# 4-UniverseOut.net
KiCad netlist of a schematic drawn in EAGLE
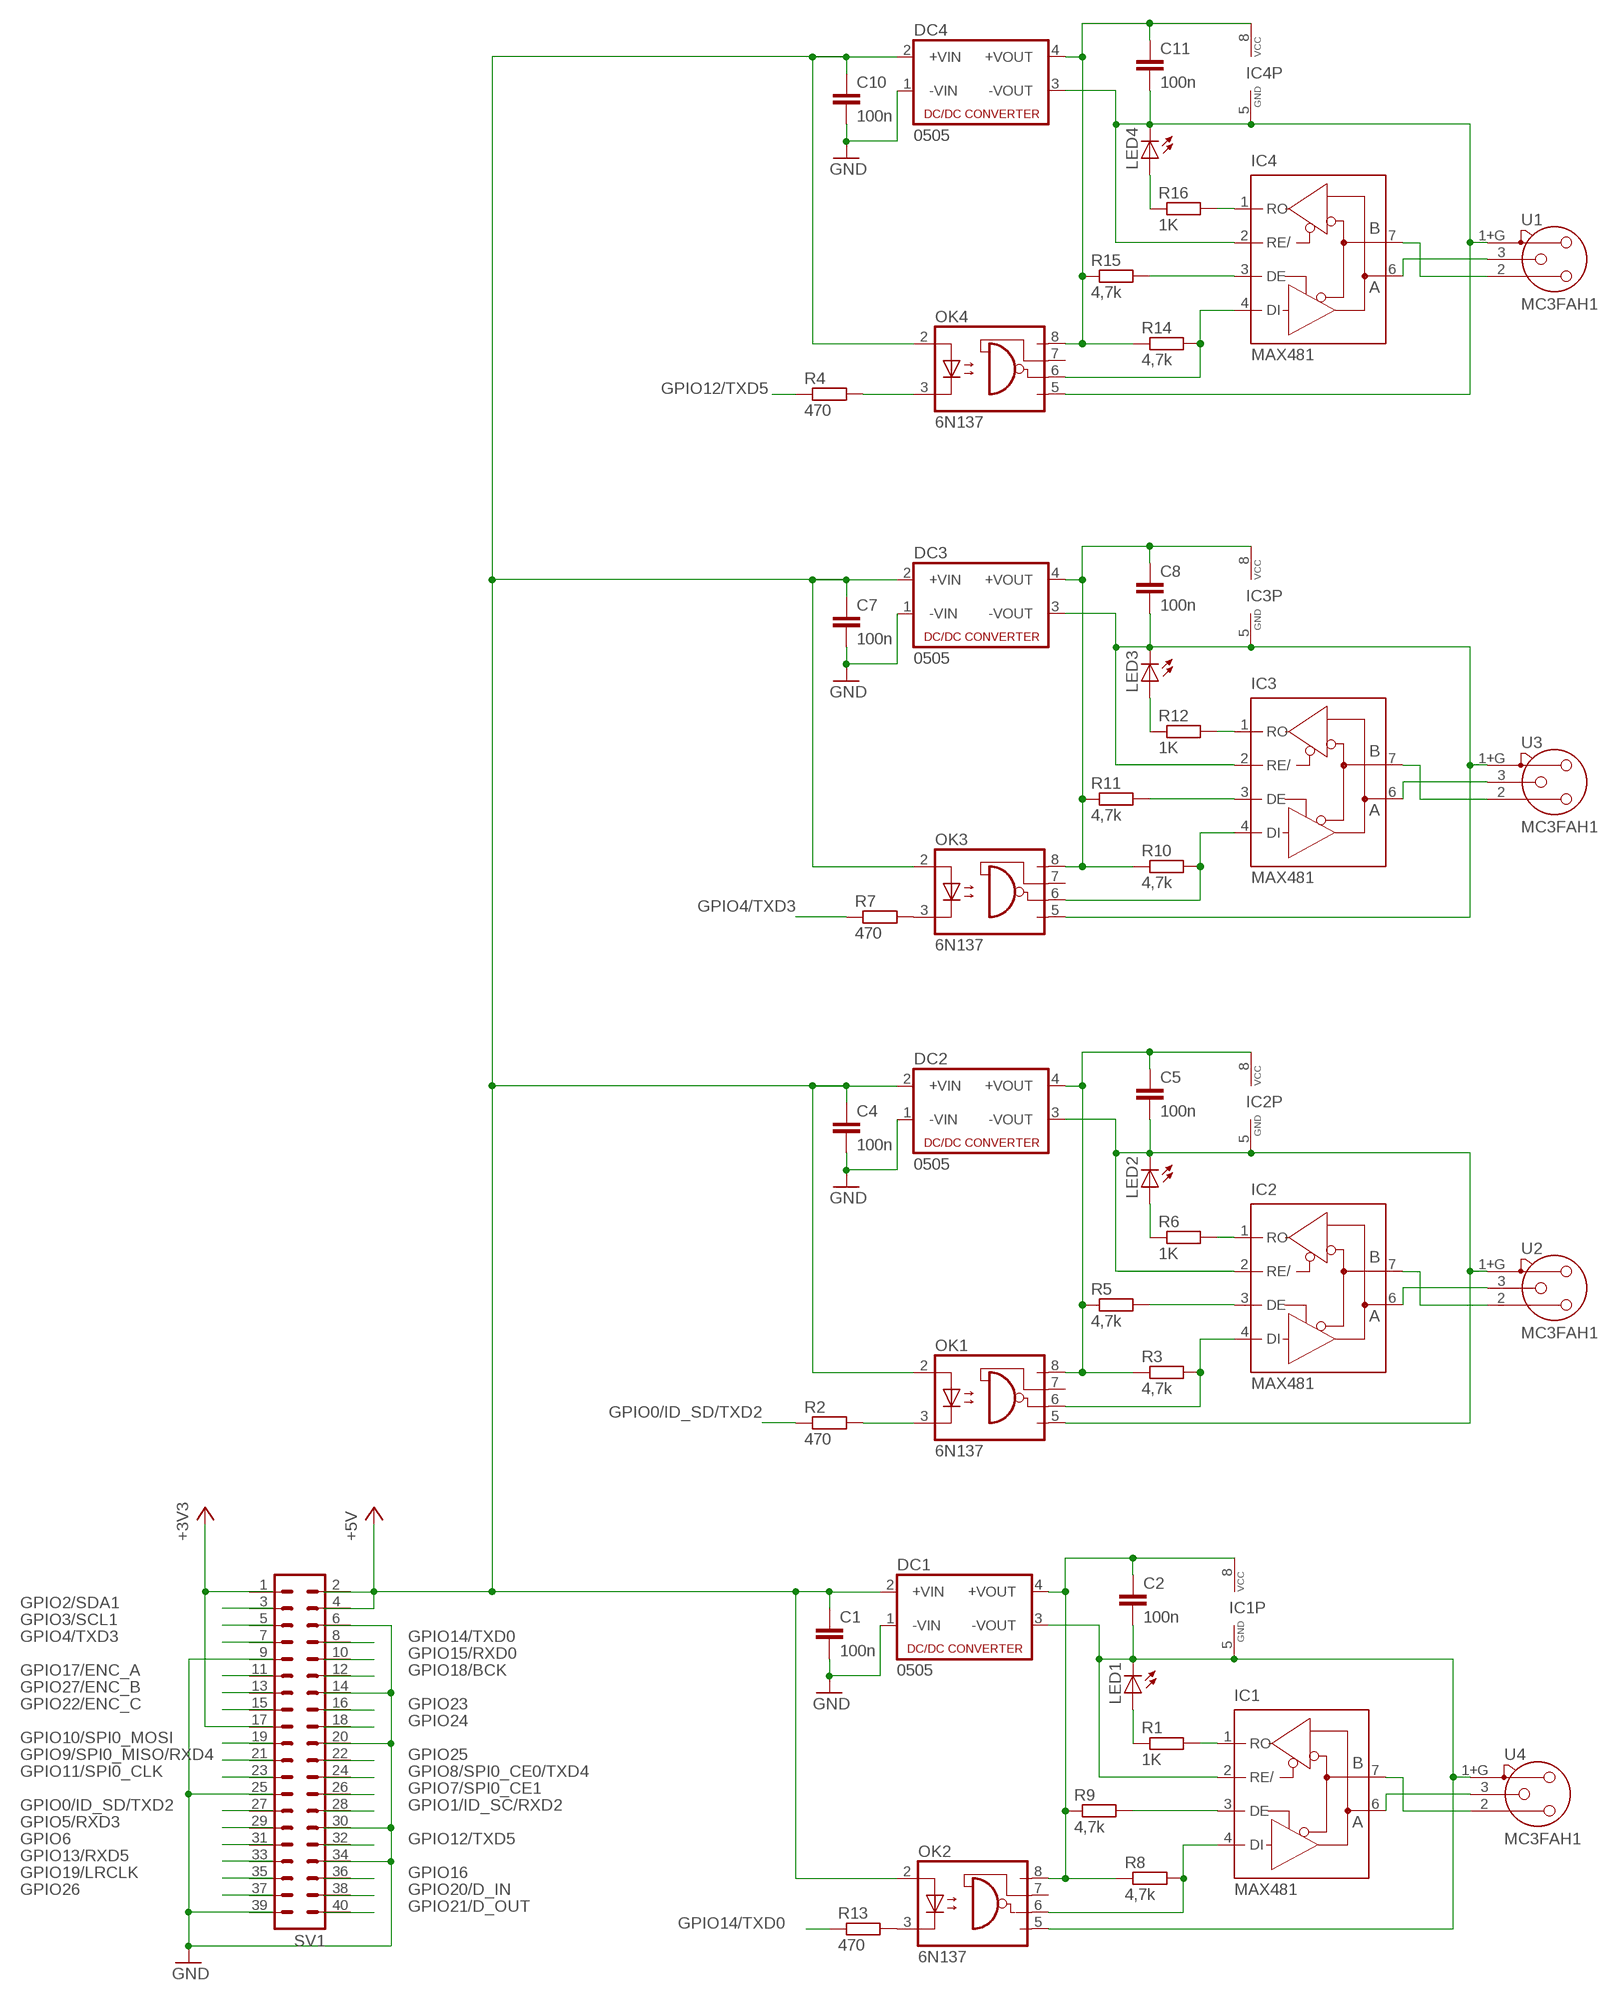
[diagram p0: schematic, sheet 1]

(export (version "E")
  (design (tool "Eeschema 10.0.6"))
  (components
    (comp (ref "C1")
      (value "100n")
      (footprint "eagle-import:C5B3")
      (libsource (lib "eagle-import") (part "C5/3"))
    )
    (comp (ref "C2")
      (value "100n")
      (footprint "eagle-import:C7.5B3")
      (libsource (lib "eagle-import") (part "C7.5/3"))
    )
    (comp (ref "C4")
      (value "100n")
      (footprint "eagle-import:C5B3")
      (libsource (lib "eagle-import") (part "C5/3"))
    )
    (comp (ref "C5")
      (value "100n")
      (footprint "eagle-import:C7.5B3")
      (libsource (lib "eagle-import") (part "C7.5/3"))
    )
    (comp (ref "C7")
      (value "100n")
      (footprint "eagle-import:C5B3")
      (libsource (lib "eagle-import") (part "C5/3"))
    )
    (comp (ref "C8")
      (value "100n")
      (footprint "eagle-import:C7.5B3")
      (libsource (lib "eagle-import") (part "C7.5/3"))
    )
    (comp (ref "C10")
      (value "100n")
      (footprint "eagle-import:C5B3")
      (libsource (lib "eagle-import") (part "C5/3"))
    )
    (comp (ref "C11")
      (value "100n")
      (footprint "eagle-import:C7.5B3")
      (libsource (lib "eagle-import") (part "C7.5/3"))
    )
    (comp (ref "DC1")
      (value "0505")
      (footprint "eagle-import:NME")
      (fields (field (name "MF") "C & D TECHNOLOGIES, INC") (field (name "MPN") "NME1205D"))
      (libsource (lib "eagle-import") (part "NME"))
    )
    (comp (ref "DC2")
      (value "0505")
      (footprint "eagle-import:NME")
      (fields (field (name "MF") "C & D TECHNOLOGIES, INC") (field (name "MPN") "NME1205D"))
      (libsource (lib "eagle-import") (part "NME"))
    )
    (comp (ref "DC3")
      (value "0505")
      (footprint "eagle-import:NME")
      (fields (field (name "MF") "C & D TECHNOLOGIES, INC") (field (name "MPN") "NME1205D"))
      (libsource (lib "eagle-import") (part "NME"))
    )
    (comp (ref "DC4")
      (value "0505")
      (footprint "eagle-import:NME")
      (fields (field (name "MF") "C & D TECHNOLOGIES, INC") (field (name "MPN") "NME1205D"))
      (libsource (lib "eagle-import") (part "NME"))
    )
    (comp (ref "IC1")
      (value "MAX481")
      (footprint "eagle-import:DIL08")
      (fields (field (name "MPN") "MAX481CPA+"))
      (libsource (lib "eagle-import") (part "MAX481CPA"))
    )
    (comp (ref "IC2")
      (value "MAX481")
      (footprint "eagle-import:DIL08")
      (fields (field (name "MPN") "MAX481CPA+"))
      (libsource (lib "eagle-import") (part "MAX481CPA"))
    )
    (comp (ref "IC3")
      (value "MAX481")
      (footprint "eagle-import:DIL08")
      (fields (field (name "MPN") "MAX481CPA+"))
      (libsource (lib "eagle-import") (part "MAX481CPA"))
    )
    (comp (ref "IC4")
      (value "MAX481")
      (footprint "eagle-import:DIL08")
      (fields (field (name "MPN") "MAX481CPA+"))
      (libsource (lib "eagle-import") (part "MAX481CPA"))
    )
    (comp (ref "LED1")
      (value "LED3MM")
      (footprint "eagle-import:LED3MM")
      (libsource (lib "eagle-import") (part "LED3MM"))
    )
    (comp (ref "LED2")
      (value "LED3MM")
      (footprint "eagle-import:LED3MM")
      (libsource (lib "eagle-import") (part "LED3MM"))
    )
    (comp (ref "LED3")
      (value "LED3MM")
      (footprint "eagle-import:LED3MM")
      (libsource (lib "eagle-import") (part "LED3MM"))
    )
    (comp (ref "LED4")
      (value "LED3MM")
      (footprint "eagle-import:LED3MM")
      (libsource (lib "eagle-import") (part "LED3MM"))
    )
    (comp (ref "OK1")
      (value "6N137")
      (footprint "eagle-import:DIL08")
      (libsource (lib "eagle-import") (part "6N137"))
    )
    (comp (ref "OK2")
      (value "6N137")
      (footprint "eagle-import:DIL08")
      (libsource (lib "eagle-import") (part "6N137"))
    )
    (comp (ref "OK3")
      (value "6N137")
      (footprint "eagle-import:DIL08")
      (libsource (lib "eagle-import") (part "6N137"))
    )
    (comp (ref "OK4")
      (value "6N137")
      (footprint "eagle-import:DIL08")
      (libsource (lib "eagle-import") (part "6N137"))
    )
    (comp (ref "R1")
      (value "1K")
      (footprint "eagle-import:0204_7")
      (libsource (lib "eagle-import") (part "R-EU_0204/7"))
    )
    (comp (ref "R2")
      (value "470")
      (footprint "eagle-import:0207_12")
      (libsource (lib "eagle-import") (part "R-EU_0207/12"))
    )
    (comp (ref "R3")
      (value "4,7k")
      (footprint "eagle-import:0204_7")
      (libsource (lib "eagle-import") (part "R-EU_0204/7"))
    )
    (comp (ref "R4")
      (value "470")
      (footprint "eagle-import:0204_7")
      (libsource (lib "eagle-import") (part "R-EU_0204/7"))
    )
    (comp (ref "R5")
      (value "4,7k")
      (footprint "eagle-import:0204_7")
      (libsource (lib "eagle-import") (part "R-EU_0204/7"))
    )
    (comp (ref "R6")
      (value "1K")
      (footprint "eagle-import:0204_7")
      (libsource (lib "eagle-import") (part "R-EU_0204/7"))
    )
    (comp (ref "R7")
      (value "470")
      (footprint "eagle-import:0204_7")
      (libsource (lib "eagle-import") (part "R-EU_0204/7"))
    )
    (comp (ref "R8")
      (value "4,7k")
      (footprint "eagle-import:0204_7")
      (libsource (lib "eagle-import") (part "R-EU_0204/7"))
    )
    (comp (ref "R9")
      (value "4,7k")
      (footprint "eagle-import:0204_7")
      (libsource (lib "eagle-import") (part "R-EU_0204/7"))
    )
    (comp (ref "R10")
      (value "4,7k")
      (footprint "eagle-import:0204_7")
      (libsource (lib "eagle-import") (part "R-EU_0204/7"))
    )
    (comp (ref "R11")
      (value "4,7k")
      (footprint "eagle-import:0204_7")
      (libsource (lib "eagle-import") (part "R-EU_0204/7"))
    )
    (comp (ref "R12")
      (value "1K")
      (footprint "eagle-import:0204_7")
      (libsource (lib "eagle-import") (part "R-EU_0204/7"))
    )
    (comp (ref "R13")
      (value "470")
      (footprint "eagle-import:0204_7")
      (libsource (lib "eagle-import") (part "R-EU_0204/7"))
    )
    (comp (ref "R14")
      (value "4,7k")
      (footprint "eagle-import:0204_7")
      (libsource (lib "eagle-import") (part "R-EU_0204/7"))
    )
    (comp (ref "R15")
      (value "4,7k")
      (footprint "eagle-import:0204_7")
      (libsource (lib "eagle-import") (part "R-EU_0204/7"))
    )
    (comp (ref "R16")
      (value "1K")
      (footprint "eagle-import:0204_7")
      (libsource (lib "eagle-import") (part "R-EU_0204/7"))
    )
    (comp (ref "SV1")
      (value "ML40")
      (footprint "eagle-import:ML40")
      (libsource (lib "eagle-import") (part "ML40"))
    )
    (comp (ref "U1")
      (value "MC3FAH1")
      (footprint "eagle-import:NC3FAH1")
      (libsource (lib "eagle-import") (part "MC3?FAH1"))
    )
    (comp (ref "U2")
      (value "MC3FAH1")
      (footprint "eagle-import:NC3FAH1")
      (libsource (lib "eagle-import") (part "MC3?FAH1"))
    )
    (comp (ref "U3")
      (value "MC3FAH1")
      (footprint "eagle-import:NC3FAH1")
      (libsource (lib "eagle-import") (part "MC3?FAH1"))
    )
    (comp (ref "U4")
      (value "MC3FAH1")
      (footprint "eagle-import:NC3FAH1")
      (libsource (lib "eagle-import") (part "MC3?FAH1"))
    )
  )
  (nets
    (net (code "1") (name "+3V3") (class "Default")
      (node (ref "SV1") (pin "1") (pinfunction "1_1") (pintype "passive"))
      (node (ref "SV1") (pin "17") (pinfunction "17_17") (pintype "passive"))
    )
    (net (code "2") (name "+5V") (class "Default")
      (node (ref "C1") (pin "1") (pinfunction "1_1") (pintype "passive"))
      (node (ref "C10") (pin "1") (pinfunction "1_1") (pintype "passive"))
      (node (ref "C4") (pin "1") (pinfunction "1_1") (pintype "passive"))
      (node (ref "C7") (pin "1") (pinfunction "1_1") (pintype "passive"))
      (node (ref "DC1") (pin "2") (pinfunction "+VIN_2") (pintype "passive"))
      (node (ref "DC2") (pin "2") (pinfunction "+VIN_2") (pintype "passive"))
      (node (ref "DC3") (pin "2") (pinfunction "+VIN_2") (pintype "passive"))
      (node (ref "DC4") (pin "2") (pinfunction "+VIN_2") (pintype "passive"))
      (node (ref "OK1") (pin "2") (pinfunction "A_2") (pintype "passive"))
      (node (ref "OK2") (pin "2") (pinfunction "A_2") (pintype "passive"))
      (node (ref "OK3") (pin "2") (pinfunction "A_2") (pintype "passive"))
      (node (ref "OK4") (pin "2") (pinfunction "A_2") (pintype "passive"))
      (node (ref "SV1") (pin "2") (pinfunction "2_2") (pintype "passive"))
      (node (ref "SV1") (pin "4") (pinfunction "4_4") (pintype "passive"))
    )
    (net (code "3") (name "/GPIO0{slash}ID_SD{slash}TXD2") (class "Default")
      (node (ref "R2") (pin "1") (pinfunction "1_1") (pintype "passive"))
      (node (ref "SV1") (pin "27") (pinfunction "27_27") (pintype "passive"))
    )
    (net (code "4") (name "/GPIO1{slash}ID_SC{slash}RXD2") (class "Default")
      (node (ref "SV1") (pin "28") (pinfunction "28_28") (pintype "passive"))
    )
    (net (code "5") (name "/GPIO2{slash}SDA1") (class "Default")
      (node (ref "SV1") (pin "3") (pinfunction "3_3") (pintype "passive"))
    )
    (net (code "6") (name "/GPIO3{slash}SCL1") (class "Default")
      (node (ref "SV1") (pin "5") (pinfunction "5_5") (pintype "passive"))
    )
    (net (code "7") (name "/GPIO4{slash}TXD3") (class "Default")
      (node (ref "R7") (pin "1") (pinfunction "1_1") (pintype "passive"))
      (node (ref "SV1") (pin "7") (pinfunction "7_7") (pintype "passive"))
    )
    (net (code "8") (name "/GPIO5{slash}RXD3") (class "Default")
      (node (ref "SV1") (pin "29") (pinfunction "29_29") (pintype "passive"))
    )
    (net (code "9") (name "/GPIO6") (class "Default")
      (node (ref "SV1") (pin "31") (pinfunction "31_31") (pintype "passive"))
    )
    (net (code "10") (name "/GPIO7{slash}SPI0_CE1") (class "Default")
      (node (ref "SV1") (pin "26") (pinfunction "26_26") (pintype "passive"))
    )
    (net (code "11") (name "/GPIO8{slash}SPI0_CE0{slash}TXD4") (class "Default")
      (node (ref "SV1") (pin "24") (pinfunction "24_24") (pintype "passive"))
    )
    (net (code "12") (name "/GPIO9{slash}SPI0_MISO{slash}RXD4") (class "Default")
      (node (ref "SV1") (pin "21") (pinfunction "21_21") (pintype "passive"))
    )
    (net (code "13") (name "/GPIO10{slash}SPI0_MOSI") (class "Default")
      (node (ref "SV1") (pin "19") (pinfunction "19_19") (pintype "passive"))
    )
    (net (code "14") (name "/GPIO11{slash}SPI0_CLK") (class "Default")
      (node (ref "SV1") (pin "23") (pinfunction "23_23") (pintype "passive"))
    )
    (net (code "15") (name "/GPIO12{slash}TXD5") (class "Default")
      (node (ref "R4") (pin "1") (pinfunction "1_1") (pintype "passive"))
      (node (ref "SV1") (pin "32") (pinfunction "32_32") (pintype "passive"))
    )
    (net (code "16") (name "/GPIO13{slash}RXD5") (class "Default")
      (node (ref "SV1") (pin "33") (pinfunction "33_33") (pintype "passive"))
    )
    (net (code "17") (name "/GPIO14{slash}TXD0") (class "Default")
      (node (ref "R13") (pin "1") (pinfunction "1_1") (pintype "passive"))
      (node (ref "SV1") (pin "8") (pinfunction "8_8") (pintype "passive"))
    )
    (net (code "18") (name "/GPIO15{slash}RXD0") (class "Default")
      (node (ref "SV1") (pin "10") (pinfunction "10_10") (pintype "passive"))
    )
    (net (code "19") (name "/GPIO16") (class "Default")
      (node (ref "SV1") (pin "36") (pinfunction "36_36") (pintype "passive"))
    )
    (net (code "20") (name "/GPIO17{slash}ENC_A") (class "Default")
      (node (ref "SV1") (pin "11") (pinfunction "11_11") (pintype "passive"))
    )
    (net (code "21") (name "/GPIO18{slash}BCK") (class "Default")
      (node (ref "SV1") (pin "12") (pinfunction "12_12") (pintype "passive"))
    )
    (net (code "22") (name "/GPIO19{slash}LRCLK") (class "Default")
      (node (ref "SV1") (pin "35") (pinfunction "35_35") (pintype "passive"))
    )
    (net (code "23") (name "/GPIO20{slash}D_IN") (class "Default")
      (node (ref "SV1") (pin "38") (pinfunction "38_38") (pintype "passive"))
    )
    (net (code "24") (name "/GPIO21{slash}D_OUT") (class "Default")
      (node (ref "SV1") (pin "40") (pinfunction "40_40") (pintype "passive"))
    )
    (net (code "25") (name "/GPIO22{slash}ENC_C") (class "Default")
      (node (ref "SV1") (pin "15") (pinfunction "15_15") (pintype "passive"))
    )
    (net (code "26") (name "/GPIO23") (class "Default")
      (node (ref "SV1") (pin "16") (pinfunction "16_16") (pintype "passive"))
    )
    (net (code "27") (name "/GPIO24") (class "Default")
      (node (ref "SV1") (pin "18") (pinfunction "18_18") (pintype "passive"))
    )
    (net (code "28") (name "/GPIO25") (class "Default")
      (node (ref "SV1") (pin "22") (pinfunction "22_22") (pintype "passive"))
    )
    (net (code "29") (name "/GPIO26") (class "Default")
      (node (ref "SV1") (pin "37") (pinfunction "37_37") (pintype "passive"))
    )
    (net (code "30") (name "/GPIO27{slash}ENC_B") (class "Default")
      (node (ref "SV1") (pin "13") (pinfunction "13_13") (pintype "passive"))
    )
    (net (code "31") (name "GND") (class "Default")
      (node (ref "C1") (pin "2") (pinfunction "2_2") (pintype "passive"))
      (node (ref "C10") (pin "2") (pinfunction "2_2") (pintype "passive"))
      (node (ref "C4") (pin "2") (pinfunction "2_2") (pintype "passive"))
      (node (ref "C7") (pin "2") (pinfunction "2_2") (pintype "passive"))
      (node (ref "DC1") (pin "1") (pinfunction "-VIN_1") (pintype "passive"))
      (node (ref "DC2") (pin "1") (pinfunction "-VIN_1") (pintype "passive"))
      (node (ref "DC3") (pin "1") (pinfunction "-VIN_1") (pintype "passive"))
      (node (ref "DC4") (pin "1") (pinfunction "-VIN_1") (pintype "passive"))
      (node (ref "SV1") (pin "14") (pinfunction "14_14") (pintype "passive"))
      (node (ref "SV1") (pin "20") (pinfunction "20_20") (pintype "passive"))
      (node (ref "SV1") (pin "25") (pinfunction "25_25") (pintype "passive"))
      (node (ref "SV1") (pin "30") (pinfunction "30_30") (pintype "passive"))
      (node (ref "SV1") (pin "34") (pinfunction "34_34") (pintype "passive"))
      (node (ref "SV1") (pin "39") (pinfunction "39_39") (pintype "passive"))
      (node (ref "SV1") (pin "6") (pinfunction "6_6") (pintype "passive"))
      (node (ref "SV1") (pin "9") (pinfunction "9_9") (pintype "passive"))
    )
    (net (code "32") (name "Net-(DC1-+VOUT)") (class "Default")
      (node (ref "C2") (pin "1") (pinfunction "1_1") (pintype "passive"))
      (node (ref "DC1") (pin "4") (pinfunction "+VOUT_4") (pintype "passive"))
      (node (ref "IC1") (pin "8") (pinfunction "VCC_8") (pintype "power_in"))
      (node (ref "OK2") (pin "8") (pinfunction "VCC_8") (pintype "passive"))
      (node (ref "R8") (pin "1") (pinfunction "1_1") (pintype "passive"))
      (node (ref "R9") (pin "1") (pinfunction "1_1") (pintype "passive"))
    )
    (net (code "33") (name "Net-(DC1--VOUT)") (class "Default")
      (node (ref "C2") (pin "2") (pinfunction "2_2") (pintype "passive"))
      (node (ref "DC1") (pin "3") (pinfunction "-VOUT_3") (pintype "passive"))
      (node (ref "IC1") (pin "2") (pinfunction "RE/_2") (pintype "input"))
      (node (ref "IC1") (pin "5") (pinfunction "GND_5") (pintype "power_in"))
      (node (ref "LED1") (pin "K") (pinfunction "C_K") (pintype "passive"))
      (node (ref "OK2") (pin "5") (pinfunction "GND_5") (pintype "passive"))
      (node (ref "U4") (pin "1+G") (pinfunction "1_1+G") (pintype "passive"))
    )
    (net (code "34") (name "Net-(DC2-+VOUT)") (class "Default")
      (node (ref "C5") (pin "1") (pinfunction "1_1") (pintype "passive"))
      (node (ref "DC2") (pin "4") (pinfunction "+VOUT_4") (pintype "passive"))
      (node (ref "IC2") (pin "8") (pinfunction "VCC_8") (pintype "power_in"))
      (node (ref "OK1") (pin "8") (pinfunction "VCC_8") (pintype "passive"))
      (node (ref "R3") (pin "1") (pinfunction "1_1") (pintype "passive"))
      (node (ref "R5") (pin "1") (pinfunction "1_1") (pintype "passive"))
    )
    (net (code "35") (name "Net-(DC2--VOUT)") (class "Default")
      (node (ref "C5") (pin "2") (pinfunction "2_2") (pintype "passive"))
      (node (ref "DC2") (pin "3") (pinfunction "-VOUT_3") (pintype "passive"))
      (node (ref "IC2") (pin "2") (pinfunction "RE/_2") (pintype "input"))
      (node (ref "IC2") (pin "5") (pinfunction "GND_5") (pintype "power_in"))
      (node (ref "LED2") (pin "K") (pinfunction "C_K") (pintype "passive"))
      (node (ref "OK1") (pin "5") (pinfunction "GND_5") (pintype "passive"))
      (node (ref "U2") (pin "1+G") (pinfunction "1_1+G") (pintype "passive"))
    )
    (net (code "36") (name "Net-(DC3-+VOUT)") (class "Default")
      (node (ref "C8") (pin "1") (pinfunction "1_1") (pintype "passive"))
      (node (ref "DC3") (pin "4") (pinfunction "+VOUT_4") (pintype "passive"))
      (node (ref "IC3") (pin "8") (pinfunction "VCC_8") (pintype "power_in"))
      (node (ref "OK3") (pin "8") (pinfunction "VCC_8") (pintype "passive"))
      (node (ref "R10") (pin "1") (pinfunction "1_1") (pintype "passive"))
      (node (ref "R11") (pin "1") (pinfunction "1_1") (pintype "passive"))
    )
    (net (code "37") (name "Net-(DC3--VOUT)") (class "Default")
      (node (ref "C8") (pin "2") (pinfunction "2_2") (pintype "passive"))
      (node (ref "DC3") (pin "3") (pinfunction "-VOUT_3") (pintype "passive"))
      (node (ref "IC3") (pin "2") (pinfunction "RE/_2") (pintype "input"))
      (node (ref "IC3") (pin "5") (pinfunction "GND_5") (pintype "power_in"))
      (node (ref "LED3") (pin "K") (pinfunction "C_K") (pintype "passive"))
      (node (ref "OK3") (pin "5") (pinfunction "GND_5") (pintype "passive"))
      (node (ref "U3") (pin "1+G") (pinfunction "1_1+G") (pintype "passive"))
    )
    (net (code "38") (name "Net-(DC4-+VOUT)") (class "Default")
      (node (ref "C11") (pin "1") (pinfunction "1_1") (pintype "passive"))
      (node (ref "DC4") (pin "4") (pinfunction "+VOUT_4") (pintype "passive"))
      (node (ref "IC4") (pin "8") (pinfunction "VCC_8") (pintype "power_in"))
      (node (ref "OK4") (pin "8") (pinfunction "VCC_8") (pintype "passive"))
      (node (ref "R14") (pin "1") (pinfunction "1_1") (pintype "passive"))
      (node (ref "R15") (pin "1") (pinfunction "1_1") (pintype "passive"))
    )
    (net (code "39") (name "Net-(DC4--VOUT)") (class "Default")
      (node (ref "C11") (pin "2") (pinfunction "2_2") (pintype "passive"))
      (node (ref "DC4") (pin "3") (pinfunction "-VOUT_3") (pintype "passive"))
      (node (ref "IC4") (pin "2") (pinfunction "RE/_2") (pintype "input"))
      (node (ref "IC4") (pin "5") (pinfunction "GND_5") (pintype "power_in"))
      (node (ref "LED4") (pin "K") (pinfunction "C_K") (pintype "passive"))
      (node (ref "OK4") (pin "5") (pinfunction "GND_5") (pintype "passive"))
      (node (ref "U1") (pin "1+G") (pinfunction "1_1+G") (pintype "passive"))
    )
    (net (code "40") (name "Net-(IC1A-A)") (class "Default")
      (node (ref "IC1") (pin "6") (pinfunction "A_6") (pintype "passive"))
      (node (ref "U4") (pin "3") (pinfunction "3_3") (pintype "passive"))
    )
    (net (code "41") (name "Net-(IC1A-B)") (class "Default")
      (node (ref "IC1") (pin "7") (pinfunction "B_7") (pintype "passive"))
      (node (ref "U4") (pin "2") (pinfunction "2_2") (pintype "passive"))
    )
    (net (code "42") (name "Net-(IC1A-DE)") (class "Default")
      (node (ref "IC1") (pin "3") (pinfunction "DE_3") (pintype "input"))
      (node (ref "R9") (pin "2") (pinfunction "2_2") (pintype "passive"))
    )
    (net (code "43") (name "Net-(IC1A-DI)") (class "Default")
      (node (ref "IC1") (pin "4") (pinfunction "DI_4") (pintype "input"))
      (node (ref "OK2") (pin "6") (pinfunction "VO_6") (pintype "passive"))
      (node (ref "R8") (pin "2") (pinfunction "2_2") (pintype "passive"))
    )
    (net (code "44") (name "Net-(IC1A-RO)") (class "Default")
      (node (ref "IC1") (pin "1") (pinfunction "RO_1") (pintype "output"))
      (node (ref "R1") (pin "2") (pinfunction "2_2") (pintype "passive"))
    )
    (net (code "45") (name "Net-(IC2A-A)") (class "Default")
      (node (ref "IC2") (pin "6") (pinfunction "A_6") (pintype "passive"))
      (node (ref "U2") (pin "3") (pinfunction "3_3") (pintype "passive"))
    )
    (net (code "46") (name "Net-(IC2A-B)") (class "Default")
      (node (ref "IC2") (pin "7") (pinfunction "B_7") (pintype "passive"))
      (node (ref "U2") (pin "2") (pinfunction "2_2") (pintype "passive"))
    )
    (net (code "47") (name "Net-(IC2A-DE)") (class "Default")
      (node (ref "IC2") (pin "3") (pinfunction "DE_3") (pintype "input"))
      (node (ref "R5") (pin "2") (pinfunction "2_2") (pintype "passive"))
    )
    (net (code "48") (name "Net-(IC2A-DI)") (class "Default")
      (node (ref "IC2") (pin "4") (pinfunction "DI_4") (pintype "input"))
      (node (ref "OK1") (pin "6") (pinfunction "VO_6") (pintype "passive"))
      (node (ref "R3") (pin "2") (pinfunction "2_2") (pintype "passive"))
    )
    (net (code "49") (name "Net-(IC2A-RO)") (class "Default")
      (node (ref "IC2") (pin "1") (pinfunction "RO_1") (pintype "output"))
      (node (ref "R6") (pin "2") (pinfunction "2_2") (pintype "passive"))
    )
    (net (code "50") (name "Net-(IC3A-A)") (class "Default")
      (node (ref "IC3") (pin "6") (pinfunction "A_6") (pintype "passive"))
      (node (ref "U3") (pin "3") (pinfunction "3_3") (pintype "passive"))
    )
    (net (code "51") (name "Net-(IC3A-B)") (class "Default")
      (node (ref "IC3") (pin "7") (pinfunction "B_7") (pintype "passive"))
      (node (ref "U3") (pin "2") (pinfunction "2_2") (pintype "passive"))
    )
    (net (code "52") (name "Net-(IC3A-DE)") (class "Default")
      (node (ref "IC3") (pin "3") (pinfunction "DE_3") (pintype "input"))
      (node (ref "R11") (pin "2") (pinfunction "2_2") (pintype "passive"))
    )
    (net (code "53") (name "Net-(IC3A-DI)") (class "Default")
      (node (ref "IC3") (pin "4") (pinfunction "DI_4") (pintype "input"))
      (node (ref "OK3") (pin "6") (pinfunction "VO_6") (pintype "passive"))
      (node (ref "R10") (pin "2") (pinfunction "2_2") (pintype "passive"))
    )
    (net (code "54") (name "Net-(IC3A-RO)") (class "Default")
      (node (ref "IC3") (pin "1") (pinfunction "RO_1") (pintype "output"))
      (node (ref "R12") (pin "2") (pinfunction "2_2") (pintype "passive"))
    )
    (net (code "55") (name "Net-(IC4A-A)") (class "Default")
      (node (ref "IC4") (pin "6") (pinfunction "A_6") (pintype "passive"))
      (node (ref "U1") (pin "3") (pinfunction "3_3") (pintype "passive"))
    )
    (net (code "56") (name "Net-(IC4A-B)") (class "Default")
      (node (ref "IC4") (pin "7") (pinfunction "B_7") (pintype "passive"))
      (node (ref "U1") (pin "2") (pinfunction "2_2") (pintype "passive"))
    )
    (net (code "57") (name "Net-(IC4A-DE)") (class "Default")
      (node (ref "IC4") (pin "3") (pinfunction "DE_3") (pintype "input"))
      (node (ref "R15") (pin "2") (pinfunction "2_2") (pintype "passive"))
    )
    (net (code "58") (name "Net-(IC4A-DI)") (class "Default")
      (node (ref "IC4") (pin "4") (pinfunction "DI_4") (pintype "input"))
      (node (ref "OK4") (pin "6") (pinfunction "VO_6") (pintype "passive"))
      (node (ref "R14") (pin "2") (pinfunction "2_2") (pintype "passive"))
    )
    (net (code "59") (name "Net-(IC4A-RO)") (class "Default")
      (node (ref "IC4") (pin "1") (pinfunction "RO_1") (pintype "output"))
      (node (ref "R16") (pin "2") (pinfunction "2_2") (pintype "passive"))
    )
    (net (code "60") (name "Net-(LED1-PadA)") (class "Default")
      (node (ref "LED1") (pin "A") (pinfunction "A_A") (pintype "passive"))
      (node (ref "R1") (pin "1") (pinfunction "1_1") (pintype "passive"))
    )
    (net (code "61") (name "Net-(LED2-PadA)") (class "Default")
      (node (ref "LED2") (pin "A") (pinfunction "A_A") (pintype "passive"))
      (node (ref "R6") (pin "1") (pinfunction "1_1") (pintype "passive"))
    )
    (net (code "62") (name "Net-(LED3-PadA)") (class "Default")
      (node (ref "LED3") (pin "A") (pinfunction "A_A") (pintype "passive"))
      (node (ref "R12") (pin "1") (pinfunction "1_1") (pintype "passive"))
    )
    (net (code "63") (name "Net-(LED4-PadA)") (class "Default")
      (node (ref "LED4") (pin "A") (pinfunction "A_A") (pintype "passive"))
      (node (ref "R16") (pin "1") (pinfunction "1_1") (pintype "passive"))
    )
    (net (code "64") (name "Net-(OK1-C)") (class "Default")
      (node (ref "OK1") (pin "3") (pinfunction "C_3") (pintype "passive"))
      (node (ref "R2") (pin "2") (pinfunction "2_2") (pintype "passive"))
    )
    (net (code "65") (name "Net-(OK2-C)") (class "Default")
      (node (ref "OK2") (pin "3") (pinfunction "C_3") (pintype "passive"))
      (node (ref "R13") (pin "2") (pinfunction "2_2") (pintype "passive"))
    )
    (net (code "66") (name "Net-(OK3-C)") (class "Default")
      (node (ref "OK3") (pin "3") (pinfunction "C_3") (pintype "passive"))
      (node (ref "R7") (pin "2") (pinfunction "2_2") (pintype "passive"))
    )
    (net (code "67") (name "Net-(OK4-C)") (class "Default")
      (node (ref "OK4") (pin "3") (pinfunction "C_3") (pintype "passive"))
      (node (ref "R4") (pin "2") (pinfunction "2_2") (pintype "passive"))
    )
    (net (code "68") (name "unconnected-(OK1-VE-Pad7)") (class "Default")
      (node (ref "OK1") (pin "7") (pinfunction "VE_7") (pintype "passive"))
    )
    (net (code "69") (name "unconnected-(OK2-VE-Pad7)") (class "Default")
      (node (ref "OK2") (pin "7") (pinfunction "VE_7") (pintype "passive"))
    )
    (net (code "70") (name "unconnected-(OK3-VE-Pad7)") (class "Default")
      (node (ref "OK3") (pin "7") (pinfunction "VE_7") (pintype "passive"))
    )
    (net (code "71") (name "unconnected-(OK4-VE-Pad7)") (class "Default")
      (node (ref "OK4") (pin "7") (pinfunction "VE_7") (pintype "passive"))
    )
  )
)
